# 24dip-8k.net
KiCad netlist of a schematic drawn in EAGLE
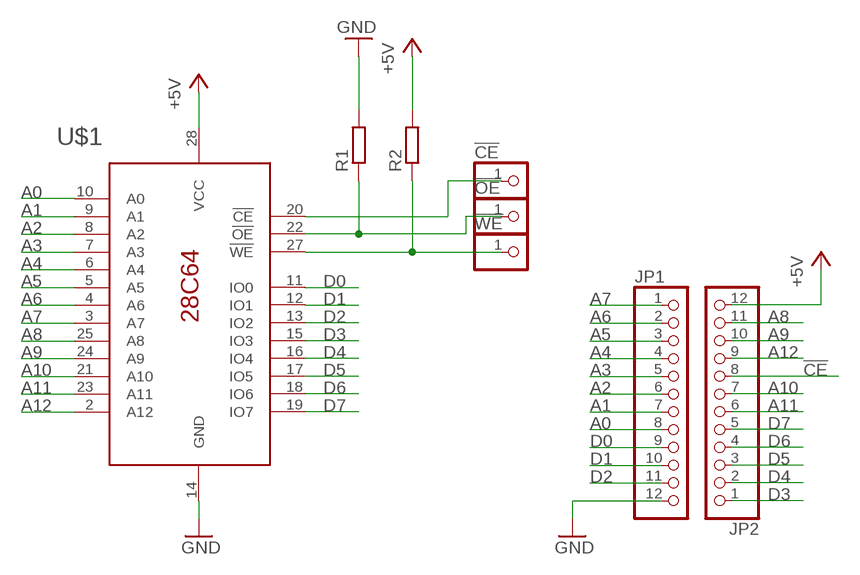
[diagram p0: schematic, sheet 1]

(export (version "E")
  (design (tool "Eeschema 10.0.6"))
  (components
    (comp (ref "!CE")
      (value "PINHD-1X1")
      (footprint "eagle-import:1X01")
      (libsource (lib "eagle-import") (part "PINHD-1X1"))
    )
    (comp (ref "!OE")
      (value "PINHD-1X1")
      (footprint "eagle-import:1X01")
      (libsource (lib "eagle-import") (part "PINHD-1X1"))
    )
    (comp (ref "!WE")
      (value "PINHD-1X1")
      (footprint "eagle-import:1X01")
      (libsource (lib "eagle-import") (part "PINHD-1X1"))
    )
    (comp (ref "JP1")
      (value "PINHD-1X12")
      (footprint "eagle-import:1X12")
      (libsource (lib "eagle-import") (part "PINHD-1X12"))
    )
    (comp (ref "JP2")
      (value "PINHD-1X12")
      (footprint "eagle-import:1X12")
      (libsource (lib "eagle-import") (part "PINHD-1X12"))
    )
    (comp (ref "R1")
      (value "R-EU_R1206")
      (footprint "eagle-import:R1206")
      (libsource (lib "eagle-import") (part "R-EU_R1206"))
    )
    (comp (ref "R2")
      (value "R-EU_R1206")
      (footprint "eagle-import:R1206")
      (libsource (lib "eagle-import") (part "R-EU_R1206"))
    )
    (comp (ref "U$1")
      (value "AT28C64B28S")
      (footprint "eagle-import:SO28W")
      (libsource (lib "eagle-import") (part "AT28C64B28S"))
    )
  )
  (nets
    (net (code "1") (name "+5V") (class "Default")
      (node (ref "JP2") (pin "12") (pinfunction "12_12") (pintype "passive"))
      (node (ref "R2") (pin "2") (pinfunction "2_2") (pintype "passive"))
      (node (ref "U$1") (pin "28") (pinfunction "VCC_28") (pintype "power_in"))
    )
    (net (code "2") (name "/A0") (class "Default")
      (node (ref "JP1") (pin "8") (pinfunction "8_8") (pintype "passive"))
      (node (ref "U$1") (pin "10") (pinfunction "A0_10") (pintype "bidirectional"))
    )
    (net (code "3") (name "/A1") (class "Default")
      (node (ref "JP1") (pin "7") (pinfunction "7_7") (pintype "passive"))
      (node (ref "U$1") (pin "9") (pinfunction "A1_9") (pintype "bidirectional"))
    )
    (net (code "4") (name "/A2") (class "Default")
      (node (ref "JP1") (pin "6") (pinfunction "6_6") (pintype "passive"))
      (node (ref "U$1") (pin "8") (pinfunction "A2_8") (pintype "bidirectional"))
    )
    (net (code "5") (name "/A3") (class "Default")
      (node (ref "JP1") (pin "5") (pinfunction "5_5") (pintype "passive"))
      (node (ref "U$1") (pin "7") (pinfunction "A3_7") (pintype "bidirectional"))
    )
    (net (code "6") (name "/A4") (class "Default")
      (node (ref "JP1") (pin "4") (pinfunction "4_4") (pintype "passive"))
      (node (ref "U$1") (pin "6") (pinfunction "A4_6") (pintype "bidirectional"))
    )
    (net (code "7") (name "/A5") (class "Default")
      (node (ref "JP1") (pin "3") (pinfunction "3_3") (pintype "passive"))
      (node (ref "U$1") (pin "5") (pinfunction "A5_5") (pintype "bidirectional"))
    )
    (net (code "8") (name "/A6") (class "Default")
      (node (ref "JP1") (pin "2") (pinfunction "2_2") (pintype "passive"))
      (node (ref "U$1") (pin "4") (pinfunction "A6_4") (pintype "bidirectional"))
    )
    (net (code "9") (name "/A7") (class "Default")
      (node (ref "JP1") (pin "1") (pinfunction "1_1") (pintype "passive"))
      (node (ref "U$1") (pin "3") (pinfunction "A7_3") (pintype "bidirectional"))
    )
    (net (code "10") (name "/A8") (class "Default")
      (node (ref "JP2") (pin "11") (pinfunction "11_11") (pintype "passive"))
      (node (ref "U$1") (pin "25") (pinfunction "A8_25") (pintype "bidirectional"))
    )
    (net (code "11") (name "/A9") (class "Default")
      (node (ref "JP2") (pin "10") (pinfunction "10_10") (pintype "passive"))
      (node (ref "U$1") (pin "24") (pinfunction "A9_24") (pintype "bidirectional"))
    )
    (net (code "12") (name "/A10") (class "Default")
      (node (ref "JP2") (pin "7") (pinfunction "7_7") (pintype "passive"))
      (node (ref "U$1") (pin "21") (pinfunction "A10_21") (pintype "bidirectional"))
    )
    (net (code "13") (name "/A11") (class "Default")
      (node (ref "JP2") (pin "6") (pinfunction "6_6") (pintype "passive"))
      (node (ref "U$1") (pin "23") (pinfunction "A11_23") (pintype "bidirectional"))
    )
    (net (code "14") (name "/A12") (class "Default")
      (node (ref "JP2") (pin "9") (pinfunction "9_9") (pintype "passive"))
      (node (ref "U$1") (pin "2") (pinfunction "A12_2") (pintype "bidirectional"))
    )
    (net (code "15") (name "/D0") (class "Default")
      (node (ref "JP1") (pin "9") (pinfunction "9_9") (pintype "passive"))
      (node (ref "U$1") (pin "11") (pinfunction "IO0_11") (pintype "bidirectional"))
    )
    (net (code "16") (name "/D1") (class "Default")
      (node (ref "JP1") (pin "10") (pinfunction "10_10") (pintype "passive"))
      (node (ref "U$1") (pin "12") (pinfunction "IO1_12") (pintype "bidirectional"))
    )
    (net (code "17") (name "/D2") (class "Default")
      (node (ref "JP1") (pin "11") (pinfunction "11_11") (pintype "passive"))
      (node (ref "U$1") (pin "13") (pinfunction "IO2_13") (pintype "bidirectional"))
    )
    (net (code "18") (name "/D3") (class "Default")
      (node (ref "JP2") (pin "1") (pinfunction "1_1") (pintype "passive"))
      (node (ref "U$1") (pin "15") (pinfunction "IO3_15") (pintype "bidirectional"))
    )
    (net (code "19") (name "/D4") (class "Default")
      (node (ref "JP2") (pin "2") (pinfunction "2_2") (pintype "passive"))
      (node (ref "U$1") (pin "16") (pinfunction "IO4_16") (pintype "bidirectional"))
    )
    (net (code "20") (name "/D5") (class "Default")
      (node (ref "JP2") (pin "3") (pinfunction "3_3") (pintype "passive"))
      (node (ref "U$1") (pin "17") (pinfunction "IO5_17") (pintype "bidirectional"))
    )
    (net (code "21") (name "/D6") (class "Default")
      (node (ref "JP2") (pin "4") (pinfunction "4_4") (pintype "passive"))
      (node (ref "U$1") (pin "18") (pinfunction "IO6_18") (pintype "bidirectional"))
    )
    (net (code "22") (name "/D7") (class "Default")
      (node (ref "JP2") (pin "5") (pinfunction "5_5") (pintype "passive"))
      (node (ref "U$1") (pin "19") (pinfunction "IO7_19") (pintype "bidirectional"))
    )
    (net (code "23") (name "/~{CE}") (class "Default")
      (node (ref "!CE") (pin "1") (pinfunction "1_1") (pintype "passive"))
      (node (ref "JP2") (pin "8") (pinfunction "8_8") (pintype "passive"))
      (node (ref "U$1") (pin "20") (pinfunction "~{CE}_20") (pintype "bidirectional"))
    )
    (net (code "24") (name "GND") (class "Default")
      (node (ref "JP1") (pin "12") (pinfunction "12_12") (pintype "passive"))
      (node (ref "R1") (pin "2") (pinfunction "2_2") (pintype "passive"))
      (node (ref "U$1") (pin "14") (pinfunction "GND_14") (pintype "power_in"))
    )
    (net (code "25") (name "Net-(U$1-~{OE})") (class "Default")
      (node (ref "!OE") (pin "1") (pinfunction "1_1") (pintype "passive"))
      (node (ref "R1") (pin "1") (pinfunction "1_1") (pintype "passive"))
      (node (ref "U$1") (pin "22") (pinfunction "~{OE}_22") (pintype "bidirectional"))
    )
    (net (code "26") (name "Net-(U$1-~{WE})") (class "Default")
      (node (ref "!WE") (pin "1") (pinfunction "1_1") (pintype "passive"))
      (node (ref "R2") (pin "1") (pinfunction "1_1") (pintype "passive"))
      (node (ref "U$1") (pin "27") (pinfunction "~{WE}_27") (pintype "bidirectional"))
    )
  )
)
